# BW1097_LEFT_OV9282.net
KiCad netlist of a schematic drawn in Altium Designer
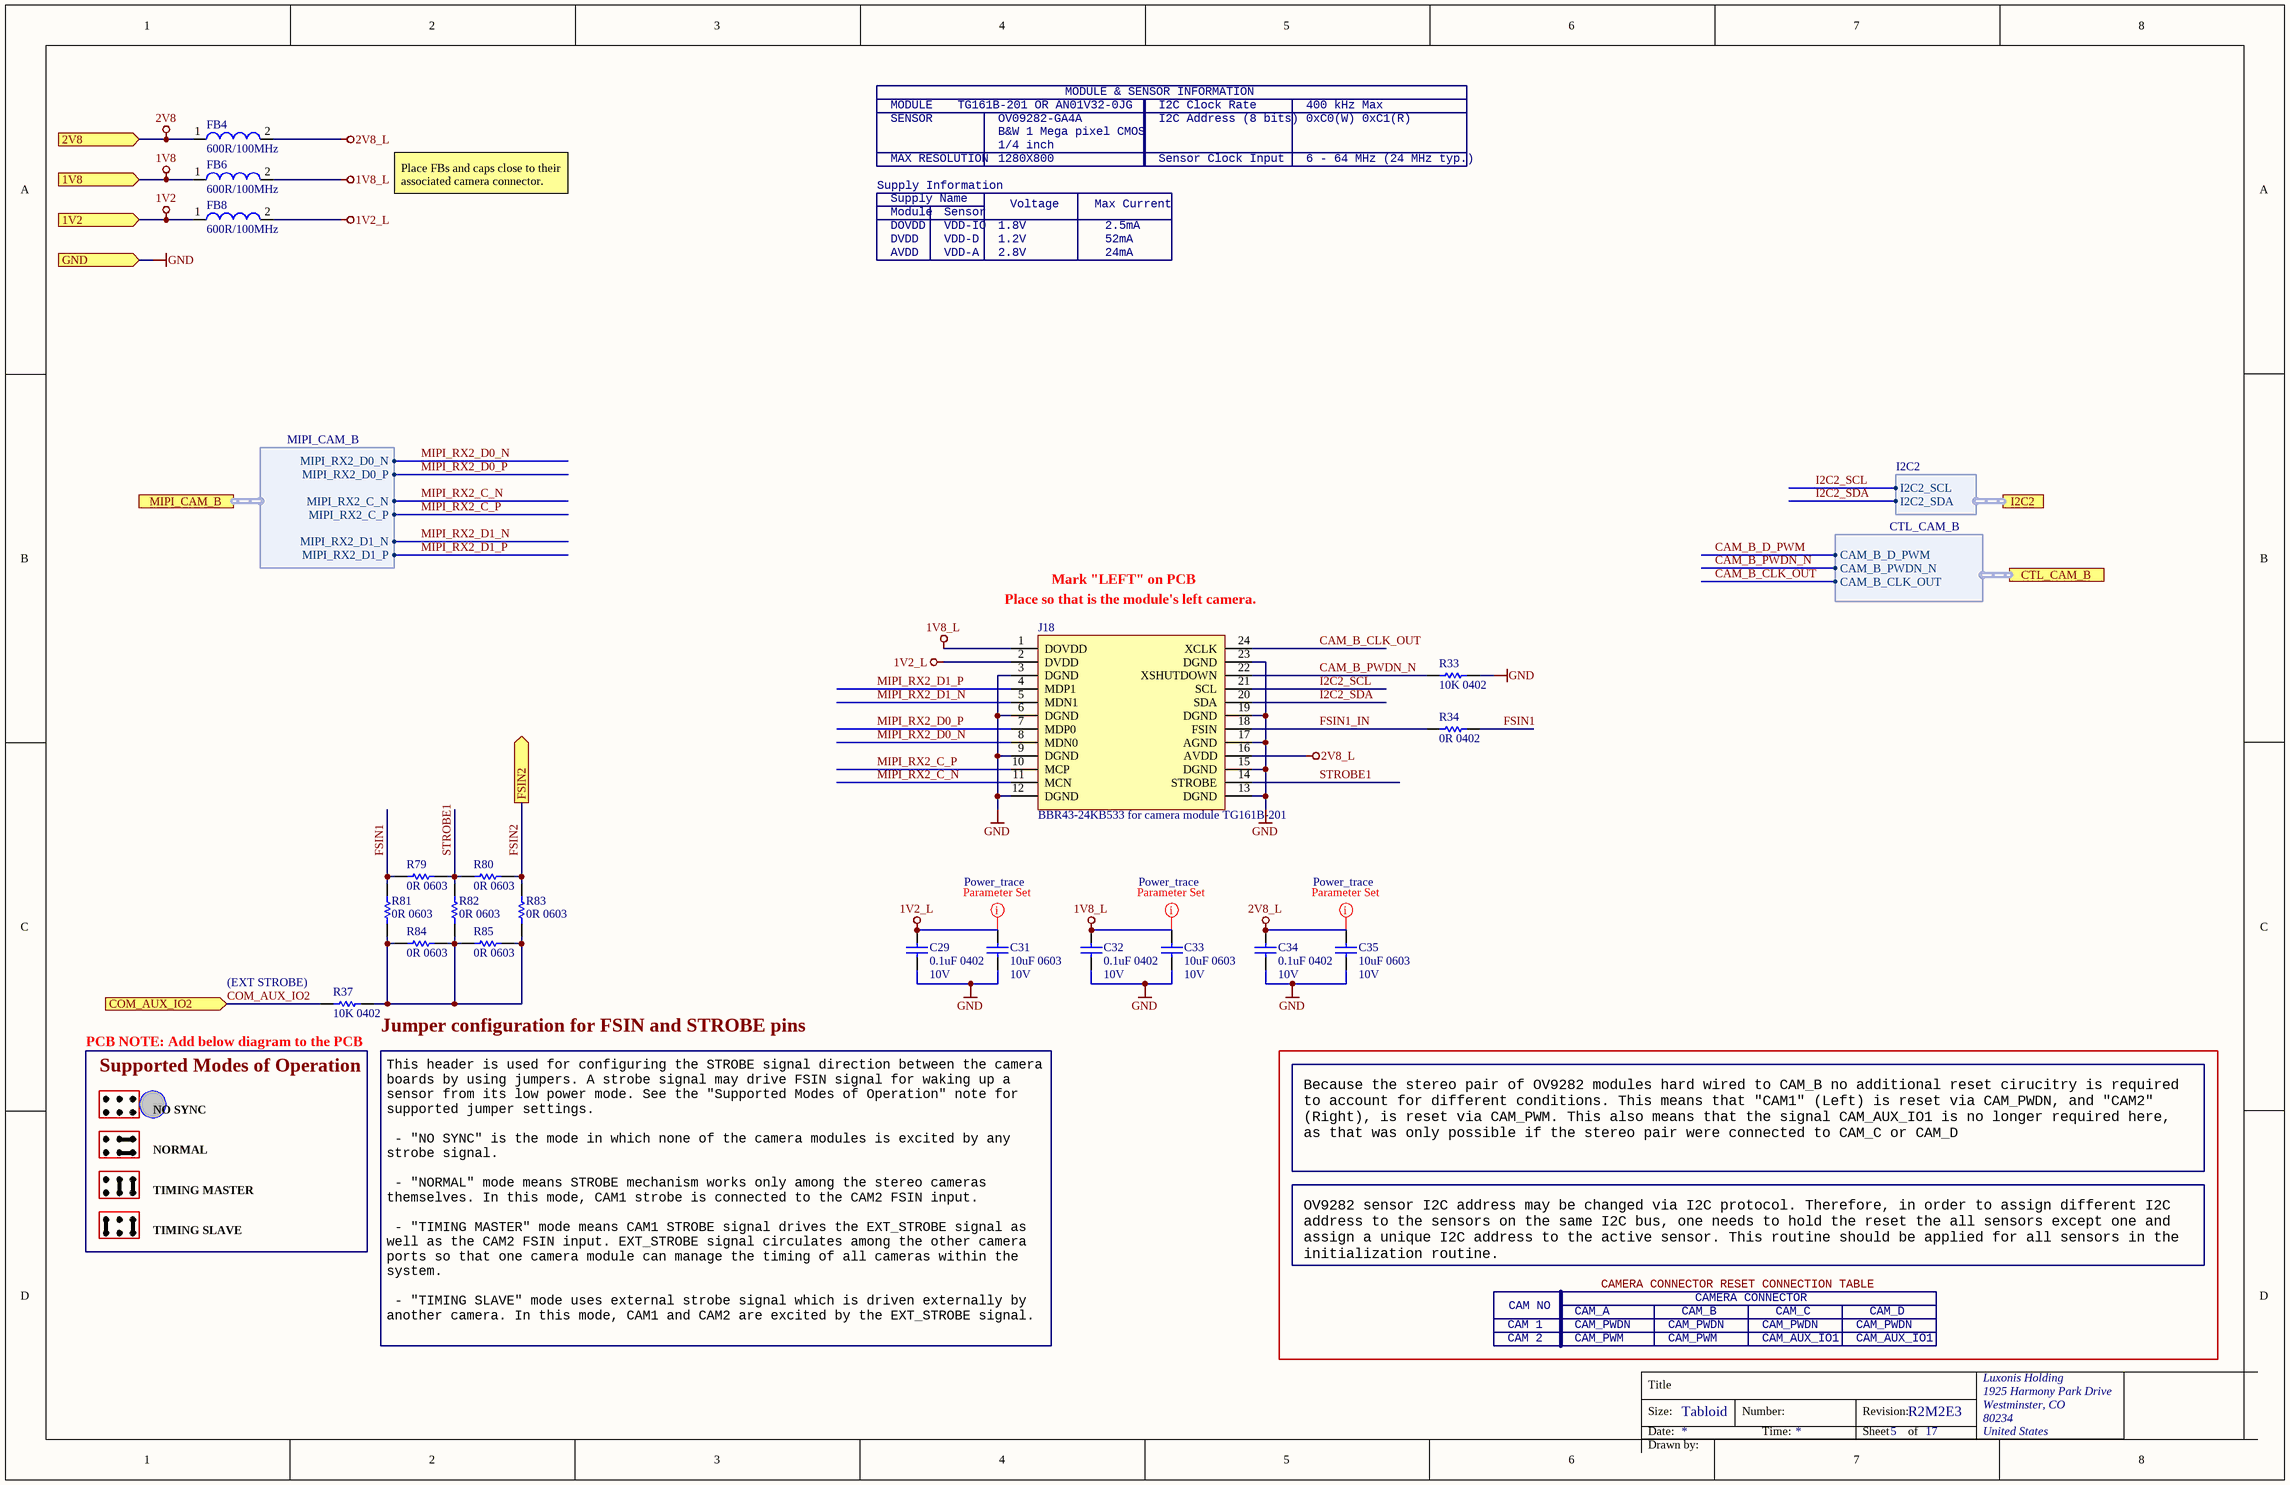
[diagram p0: BW1097_LEFT_OV9282.SchDoc]

(export (version "E")
  (design (tool "Eeschema 10.0.6"))
  (components
    (comp (ref "C29")
      (value "0.1uF 0402")
      (footprint "CAP_Altium_Vault_Generic:CAPC0402(1005)70_N")
      (description "CAP CER 0.1UF 10V X7R 0402 5%")
      (fields (field (name "TOLERANCE") "5%") (field (name "VOLTAGE RATING") "10V"))
      (libsource (lib "LuxonisMaster") (part "GRM155R71A104JA01D"))
    )
    (comp (ref "C31")
      (value "10uF 0603")
      (footprint "CAP_Altium_Vault_Generic:CAPC0603(1608)100_N")
      (description "CAP CER 10UF 10V X5R 0603 20%")
      (fields (field (name "TOLERANCE") "20%") (field (name "VOLTAGE RATING") "10V"))
      (libsource (lib "LuxonisMaster") (part "GRM188R61A106ME69D"))
    )
    (comp (ref "C32")
      (value "0.1uF 0402")
      (footprint "CAP_Altium_Vault_Generic:CAPC0402(1005)70_N")
      (description "CAP CER 0.1UF 10V X7R 0402 5%")
      (fields (field (name "TOLERANCE") "5%") (field (name "VOLTAGE RATING") "10V"))
      (libsource (lib "LuxonisMaster") (part "GRM155R71A104JA01D"))
    )
    (comp (ref "C33")
      (value "10uF 0603")
      (footprint "CAP_Altium_Vault_Generic:CAPC0603(1608)100_N")
      (description "CAP CER 10UF 10V X5R 0603 20%")
      (fields (field (name "TOLERANCE") "20%") (field (name "VOLTAGE RATING") "10V"))
      (libsource (lib "LuxonisMaster") (part "GRM188R61A106ME69D"))
    )
    (comp (ref "C34")
      (value "0.1uF 0402")
      (footprint "CAP_Altium_Vault_Generic:CAPC0402(1005)70_N")
      (description "CAP CER 0.1UF 10V X7R 0402 5%")
      (fields (field (name "TOLERANCE") "5%") (field (name "VOLTAGE RATING") "10V"))
      (libsource (lib "LuxonisMaster") (part "GRM155R71A104JA01D"))
    )
    (comp (ref "C35")
      (value "10uF 0603")
      (footprint "CAP_Altium_Vault_Generic:CAPC0603(1608)100_N")
      (description "CAP CER 10UF 10V X5R 0603 20%")
      (fields (field (name "TOLERANCE") "20%") (field (name "VOLTAGE RATING") "10V"))
      (libsource (lib "LuxonisMaster") (part "GRM188R61A106ME69D"))
    )
    (comp (ref "FB4")
      (value "600R/100MHz")
      (footprint "LuxonisMaster:2508056017Y2")
      (description "FERRITE BEAD, 0.1OHM, 2A, 0805, 600R/100MHz")
      (fields (field (name "TOLERANCE") "25%"))
      (libsource (lib "LuxonisMaster") (part "2508056017Y2"))
    )
    (comp (ref "FB6")
      (value "600R/100MHz")
      (footprint "LuxonisMaster:2508056017Y2")
      (description "FERRITE BEAD, 0.1OHM, 2A, 0805, 600R/100MHz")
      (fields (field (name "TOLERANCE") "25%"))
      (libsource (lib "LuxonisMaster") (part "2508056017Y2"))
    )
    (comp (ref "FB8")
      (value "600R/100MHz")
      (footprint "LuxonisMaster:2508056017Y2")
      (description "FERRITE BEAD, 0.1OHM, 2A, 0805, 600R/100MHz")
      (fields (field (name "TOLERANCE") "25%"))
      (libsource (lib "LuxonisMaster") (part "2508056017Y2"))
    )
    (comp (ref "J18")
      (value "BBR43-24KB533 for camera module TG161B-201")
      (footprint "LuxonisMaster:TG161B-201_HD")
      (description "CONN 24 way, 2 row board to board connector SMD")
      (fields (field (name "MANUFACTURER") "ACON"))
      (libsource (lib "LuxonisMaster") (part "TG161B-201_Connector"))
    )
    (comp (ref "R33")
      (value "10K 0402")
      (footprint "RES_Altium_Vault_Generic:RESC0402(1005)_N")
      (fields (field (name "TOLERANCE") "1%"))
      (libsource (lib "LuxonisMaster") (part "RC0402FR-1310KL"))
    )
    (comp (ref "R34")
      (value "0R 0402")
      (footprint "RES_Altium_Vault_Generic:RESC0402(1005)_N")
      (description "RES SMD 0 OHM JUMPER 1/16W 0402")
      (fields (field (name "TOLERANCE") "5%"))
      (libsource (lib "LuxonisMaster") (part "CRCW04020000Z0ED"))
    )
    (comp (ref "R37")
      (value "10K 0402")
      (footprint "RES_Altium_Vault_Generic:RESC0402(1005)_N")
      (fields (field (name "TOLERANCE") "1%"))
      (libsource (lib "LuxonisMaster") (part "RC0402FR-1310KL"))
    )
    (comp (ref "R79")
      (value "0R 0603")
      (footprint "RES_Altium_Vault_Generic:RESC0603(1608)_N")
      (fields (field (name "TOLERANCE") "5%"))
      (libsource (lib "LuxonisMaster") (part "CRCW06030000Z0EA"))
    )
    (comp (ref "R80")
      (value "0R 0603")
      (footprint "RES_Altium_Vault_Generic:RESC0603(1608)_N")
      (fields (field (name "TOLERANCE") "5%"))
      (libsource (lib "LuxonisMaster") (part "CRCW06030000Z0EA"))
    )
    (comp (ref "R81")
      (value "0R 0603")
      (footprint "RES_Altium_Vault_Generic:RESC0603(1608)_N")
      (fields (field (name "TOLERANCE") "5%"))
      (libsource (lib "LuxonisMaster") (part "CRCW06030000Z0EA"))
    )
    (comp (ref "R82")
      (value "0R 0603")
      (footprint "RES_Altium_Vault_Generic:RESC0603(1608)_N")
      (fields (field (name "TOLERANCE") "5%"))
      (libsource (lib "LuxonisMaster") (part "CRCW06030000Z0EA"))
    )
    (comp (ref "R83")
      (value "0R 0603")
      (footprint "RES_Altium_Vault_Generic:RESC0603(1608)_N")
      (fields (field (name "TOLERANCE") "5%"))
      (libsource (lib "LuxonisMaster") (part "CRCW06030000Z0EA"))
    )
    (comp (ref "R84")
      (value "0R 0603")
      (footprint "RES_Altium_Vault_Generic:RESC0603(1608)_N")
      (fields (field (name "TOLERANCE") "5%"))
      (libsource (lib "LuxonisMaster") (part "CRCW06030000Z0EA"))
    )
    (comp (ref "R85")
      (value "0R 0603")
      (footprint "RES_Altium_Vault_Generic:RESC0603(1608)_N")
      (fields (field (name "TOLERANCE") "5%"))
      (libsource (lib "LuxonisMaster") (part "CRCW06030000Z0EA"))
    )
  )
  (nets
    (net (code "4") (name "/CAM_B_CLK_OUT") (class "Default")
      (node (ref "J18") (pin "24") (pinfunction "XCLK_24") (pintype "passive"))
    )
    (net (code "6") (name "/CAM_B_PWDN_N") (class "Default")
      (node (ref "J18") (pin "22") (pinfunction "XSHUTDOWN_22") (pintype "passive"))
      (node (ref "R33") (pin "1") (pinfunction "1_1") (pintype "passive"))
    )
    (net (code "7") (name "/COM_AUX_IO2") (class "Default")
      (node (ref "R37") (pin "1") (pinfunction "1_1") (pintype "passive"))
    )
    (net (code "8") (name "/FSIN1") (class "Default")
      (node (ref "R34") (pin "2") (pinfunction "2_2") (pintype "passive"))
      (node (ref "R79") (pin "1") (pinfunction "1_1") (pintype "passive"))
      (node (ref "R81") (pin "2") (pinfunction "2_2") (pintype "passive"))
    )
    (net (code "9") (name "/FSIN1_IN") (class "Default")
      (node (ref "J18") (pin "18") (pinfunction "FSIN_18") (pintype "passive"))
      (node (ref "R34") (pin "1") (pinfunction "1_1") (pintype "passive"))
    )
    (net (code "10") (name "/FSIN2") (class "Default")
      (node (ref "R80") (pin "2") (pinfunction "2_2") (pintype "passive"))
      (node (ref "R83") (pin "2") (pinfunction "2_2") (pintype "passive"))
    )
    (net (code "11") (name "/I2C2_SCL") (class "Default")
      (node (ref "J18") (pin "21") (pinfunction "SCL_21") (pintype "passive"))
    )
    (net (code "12") (name "/I2C2_SDA") (class "Default")
      (node (ref "J18") (pin "20") (pinfunction "SDA_20") (pintype "passive"))
    )
    (net (code "13") (name "/MIPI_RX2_C_N") (class "Default")
      (node (ref "J18") (pin "11") (pinfunction "MCN_11") (pintype "passive"))
    )
    (net (code "14") (name "/MIPI_RX2_C_P") (class "Default")
      (node (ref "J18") (pin "10") (pinfunction "MCP_10") (pintype "passive"))
    )
    (net (code "15") (name "/MIPI_RX2_D0_N") (class "Default")
      (node (ref "J18") (pin "8") (pinfunction "MDN0_8") (pintype "passive"))
    )
    (net (code "16") (name "/MIPI_RX2_D0_P") (class "Default")
      (node (ref "J18") (pin "7") (pinfunction "MDP0_7") (pintype "passive"))
    )
    (net (code "17") (name "/MIPI_RX2_D1_N") (class "Default")
      (node (ref "J18") (pin "5") (pinfunction "MDN1_5") (pintype "passive"))
    )
    (net (code "18") (name "/MIPI_RX2_D1_P") (class "Default")
      (node (ref "J18") (pin "4") (pinfunction "MDP1_4") (pintype "passive"))
    )
    (net (code "19") (name "/STROBE1") (class "Default")
      (node (ref "J18") (pin "14") (pinfunction "STROBE_14") (pintype "passive"))
      (node (ref "R79") (pin "2") (pinfunction "2_2") (pintype "passive"))
      (node (ref "R80") (pin "1") (pinfunction "1_1") (pintype "passive"))
      (node (ref "R82") (pin "2") (pinfunction "2_2") (pintype "passive"))
    )
    (net (code "23") (name "1V2") (class "Default")
      (node (ref "FB8") (pin "1") (pinfunction "1_1") (pintype "passive"))
    )
    (net (code "24") (name "1V2_L") (class "Default")
      (node (ref "C29") (pin "2") (pinfunction "2_2") (pintype "passive"))
      (node (ref "C31") (pin "2") (pinfunction "2_2") (pintype "passive"))
      (node (ref "FB8") (pin "2") (pinfunction "2_2") (pintype "passive"))
      (node (ref "J18") (pin "2") (pinfunction "DVDD_2") (pintype "passive"))
    )
    (net (code "25") (name "1V8") (class "Default")
      (node (ref "FB6") (pin "1") (pinfunction "1_1") (pintype "passive"))
    )
    (net (code "26") (name "1V8_L") (class "Default")
      (node (ref "C32") (pin "2") (pinfunction "2_2") (pintype "passive"))
      (node (ref "C33") (pin "2") (pinfunction "2_2") (pintype "passive"))
      (node (ref "FB6") (pin "2") (pinfunction "2_2") (pintype "passive"))
      (node (ref "J18") (pin "1") (pinfunction "DOVDD_1") (pintype "passive"))
    )
    (net (code "27") (name "2V8") (class "Default")
      (node (ref "FB4") (pin "1") (pinfunction "1_1") (pintype "passive"))
    )
    (net (code "28") (name "2V8_L") (class "Default")
      (node (ref "C34") (pin "2") (pinfunction "2_2") (pintype "passive"))
      (node (ref "C35") (pin "2") (pinfunction "2_2") (pintype "passive"))
      (node (ref "FB4") (pin "2") (pinfunction "2_2") (pintype "passive"))
      (node (ref "J18") (pin "16") (pinfunction "AVDD_16") (pintype "passive"))
    )
    (net (code "29") (name "GND") (class "Default")
      (node (ref "C29") (pin "1") (pinfunction "1_1") (pintype "passive"))
      (node (ref "C31") (pin "1") (pinfunction "1_1") (pintype "passive"))
      (node (ref "C32") (pin "1") (pinfunction "1_1") (pintype "passive"))
      (node (ref "C33") (pin "1") (pinfunction "1_1") (pintype "passive"))
      (node (ref "C34") (pin "1") (pinfunction "1_1") (pintype "passive"))
      (node (ref "C35") (pin "1") (pinfunction "1_1") (pintype "passive"))
      (node (ref "J18") (pin "12") (pinfunction "DGND_12") (pintype "passive"))
      (node (ref "J18") (pin "13") (pinfunction "DGND_13") (pintype "passive"))
      (node (ref "J18") (pin "15") (pinfunction "DGND_15") (pintype "passive"))
      (node (ref "J18") (pin "17") (pinfunction "AGND_17") (pintype "passive"))
      (node (ref "J18") (pin "19") (pinfunction "DGND_19") (pintype "passive"))
      (node (ref "J18") (pin "23") (pinfunction "DGND_23") (pintype "passive"))
      (node (ref "J18") (pin "3") (pinfunction "DGND_3") (pintype "passive"))
      (node (ref "J18") (pin "6") (pinfunction "DGND_6") (pintype "passive"))
      (node (ref "J18") (pin "9") (pinfunction "DGND_9") (pintype "passive"))
      (node (ref "R33") (pin "2") (pinfunction "2_2") (pintype "passive"))
    )
    (net (code "30") (name "Net-(R37-Pad2)") (class "Default")
      (node (ref "R37") (pin "2") (pinfunction "2_2") (pintype "passive"))
      (node (ref "R81") (pin "1") (pinfunction "1_1") (pintype "passive"))
      (node (ref "R82") (pin "1") (pinfunction "1_1") (pintype "passive"))
      (node (ref "R83") (pin "1") (pinfunction "1_1") (pintype "passive"))
      (node (ref "R84") (pin "1") (pinfunction "1_1") (pintype "passive"))
      (node (ref "R84") (pin "2") (pinfunction "2_2") (pintype "passive"))
      (node (ref "R85") (pin "1") (pinfunction "1_1") (pintype "passive"))
      (node (ref "R85") (pin "2") (pinfunction "2_2") (pintype "passive"))
    )
  )
)
